# LPCB281_-_POWER.net
KiCad netlist of a schematic drawn in Altium Designer
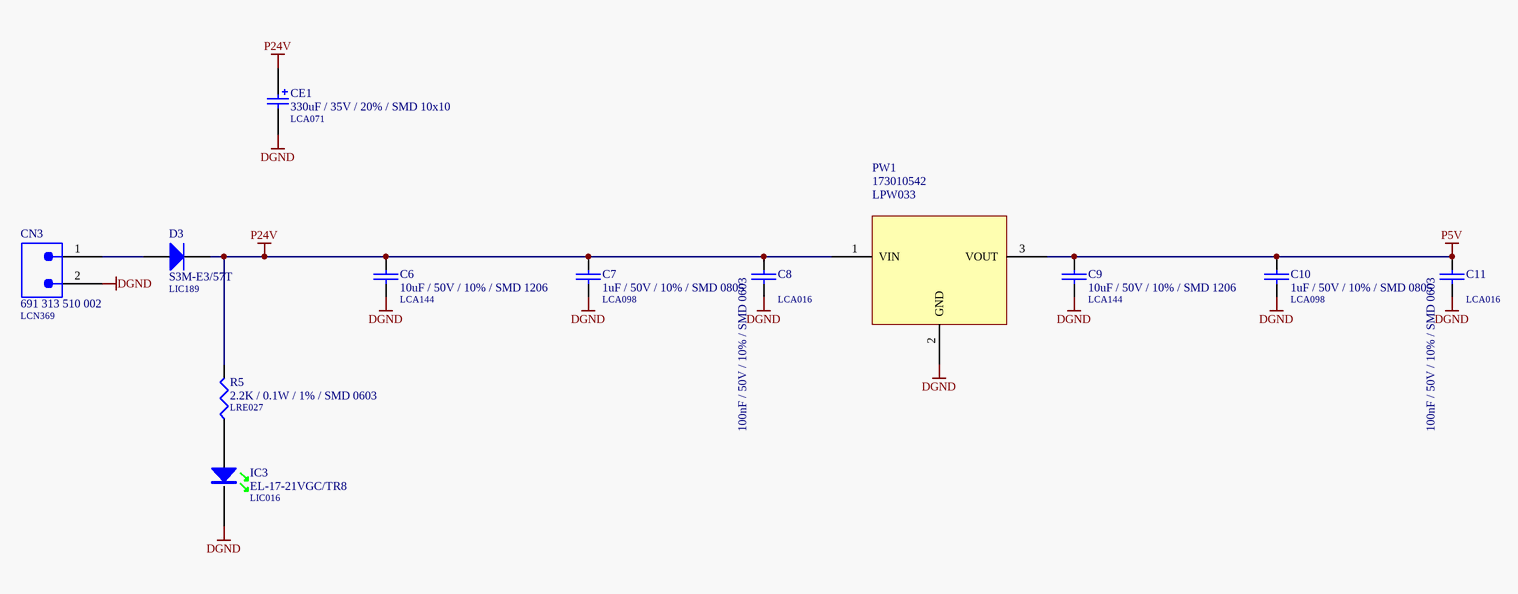
[diagram p0: LPCB281 - POWER.SchDoc]

(export (version "E")
  (design (tool "Eeschema 10.0.6"))
  (components
    (comp (ref "C6")
      (value "10uF / 50V / 10% / SMD 1206")
      (footprint "LFP043__CC3216-1206")
      (description "Capacitor, Ceramic Chip, 10uF, 50V, X5R, 10%, SMD 1206 [LCA144]")
      (fields (field (name "LDL_NUMBER") "LCA144"))
      (libsource (lib "LDL_Capacitors") (part "10uF / 50V / 10% / SMD 1206"))
    )
    (comp (ref "C7")
      (value "1uF / 50V / 10% / SMD 0805")
      (footprint "LFP010__CC2012-0805-IPC7351_B")
      (description "Capacitor, Ceramic Chip, 1uF, 50V, SMD 0805 [LCA098]")
      (fields (field (name "LDL_NUMBER") "LCA098"))
      (libsource (lib "LDL_Capacitors") (part "1uF / 50V / 10% / SMD 0805"))
    )
    (comp (ref "C8")
      (value "100nF / 50V / 10% / SMD 0603")
      (footprint "LFP011__CC1608-0603-IPC7351_B")
      (description "Capacitor, Ceramic Chip, 100nF (0.1uF), 50V, 5%, SMD 0603 [LCA016]")
      (fields (field (name "LDL_NUMBER") "LCA016"))
      (libsource (lib "LDL_Capacitors") (part "100nF / 50V / 10% / SMD 0603"))
    )
    (comp (ref "C9")
      (value "10uF / 50V / 10% / SMD 1206")
      (footprint "LFP043__CC3216-1206")
      (description "Capacitor, Ceramic Chip, 10uF, 50V, X5R, 10%, SMD 1206 [LCA144]")
      (fields (field (name "LDL_NUMBER") "LCA144"))
      (libsource (lib "LDL_Capacitors") (part "10uF / 50V / 10% / SMD 1206"))
    )
    (comp (ref "C10")
      (value "1uF / 50V / 10% / SMD 0805")
      (footprint "LFP010__CC2012-0805-IPC7351_B")
      (description "Capacitor, Ceramic Chip, 1uF, 50V, SMD 0805 [LCA098]")
      (fields (field (name "LDL_NUMBER") "LCA098"))
      (libsource (lib "LDL_Capacitors") (part "1uF / 50V / 10% / SMD 0805"))
    )
    (comp (ref "C11")
      (value "100nF / 50V / 10% / SMD 0603")
      (footprint "LFP011__CC1608-0603-IPC7351_B")
      (description "Capacitor, Ceramic Chip, 100nF (0.1uF), 50V, 5%, SMD 0603 [LCA016]")
      (fields (field (name "LDL_NUMBER") "LCA016"))
      (libsource (lib "LDL_Capacitors") (part "100nF / 50V / 10% / SMD 0603"))
    )
    (comp (ref "CE1")
      (value "330uF / 35V / 20% / SMD 10x10")
      (footprint "LFP041__NICHICON_WT_10X10")
      (description "Capacitor, Aluminum Electrolytic, 330uF, 35V, 20%, SMD (10mm x 10mm) [LCA071]")
      (fields (field (name "LDL_NUMBER") "LCA071"))
      (libsource (lib "LDL_Capacitors") (part "330uF / 35V / 20% / SMD 10x10"))
    )
    (comp (ref "CN3")
      (value "691 313 510 002")
      (footprint "691 313 510 002")
      (description "Connector, Pluggable Terminal Block, 5.08mm, 2 Way, PTH")
      (fields (field (name "LDL_NUMBER") "LCN369"))
      (libsource (lib "LDL_Connectors") (part "691 313 510 002"))
    )
    (comp (ref "D3")
      (value "S3M-E3/57T")
      (footprint "LFP040__DO-214AB")
      (description "Diode, General Purpose Rectifier, 3A, 200V, SMD DO-214AB [LIC189]")
      (fields (field (name "LDL_NUMBER") "LIC189"))
      (libsource (lib "LDL_Semiconductors") (part "S3M-E3/57T"))
    )
    (comp (ref "IC3")
      (value "EL-17-21VGC/TR8")
      (footprint "CR2012-0805-LED")
      (description "LED, SMD, 0805 Green [LIC016]")
      (fields (field (name "LDL_NUMBER") "LIC016"))
      (libsource (lib "LDL_Semiconductors") (part "EL-17-21VGC/TR8"))
    )
    (comp (ref "PW1")
      (value "173010542")
      (footprint "173010542")
      (fields (field (name "LDL_NUMBER") "LPW033"))
      (libsource (lib "LDL_Power") (part "173010542"))
    )
    (comp (ref "R5")
      (value "2.2K / 0.1W / 1% / SMD 0603")
      (footprint "LFP020__CR1608-0603-IPC7351_B")
      (description "Resistor, Ceramic Chip, 2.2K, 0.1W, 1%, SMD 0603 [LRE027]")
      (fields (field (name "LDL_NUMBER") "LRE027"))
      (libsource (lib "LDL_Resistors") (part "2.2K / 0.1W / 1% / SMD 0603"))
    )
  )
  (nets
    (net (code "1") (name "DGND") (class "Default")
      (node (ref "C10") (pin "2") (pintype "passive"))
      (node (ref "C11") (pin "2") (pintype "passive"))
      (node (ref "C6") (pin "2") (pintype "passive"))
      (node (ref "C7") (pin "2") (pintype "passive"))
      (node (ref "C8") (pin "2") (pintype "passive"))
      (node (ref "C9") (pin "2") (pintype "passive"))
      (node (ref "CE1") (pin "2") (pinfunction "2_2") (pintype "passive"))
      (node (ref "CN3") (pin "2") (pinfunction "2_2") (pintype "passive"))
      (node (ref "IC3") (pin "K") (pintype "passive"))
      (node (ref "PW1") (pin "2") (pinfunction "GND_2") (pintype "passive"))
    )
    (net (code "2") (name "Net-(D3-A)") (class "Default")
      (node (ref "CN3") (pin "1") (pinfunction "1_1") (pintype "passive"))
      (node (ref "D3") (pin "2") (pinfunction "A_2") (pintype "passive"))
    )
    (net (code "3") (name "Net-(IC3-PadA)") (class "Default")
      (node (ref "IC3") (pin "A") (pintype "passive"))
      (node (ref "R5") (pin "1") (pintype "passive"))
    )
    (net (code "4") (name "P5V") (class "Default")
      (node (ref "C10") (pin "1") (pintype "passive"))
      (node (ref "C11") (pin "1") (pintype "passive"))
      (node (ref "C9") (pin "1") (pintype "passive"))
      (node (ref "PW1") (pin "3") (pinfunction "VOUT_3") (pintype "passive"))
    )
    (net (code "5") (name "P24V") (class "Default")
      (node (ref "C6") (pin "1") (pintype "passive"))
      (node (ref "C7") (pin "1") (pintype "passive"))
      (node (ref "C8") (pin "1") (pintype "passive"))
      (node (ref "CE1") (pin "1") (pinfunction "1_1") (pintype "passive"))
      (node (ref "D3") (pin "1") (pinfunction "K_1") (pintype "passive"))
      (node (ref "PW1") (pin "1") (pinfunction "VIN_1") (pintype "passive"))
      (node (ref "R5") (pin "2") (pintype "passive"))
    )
  )
)
